# Central_Control.net
KiCad netlist of a schematic drawn in EAGLE
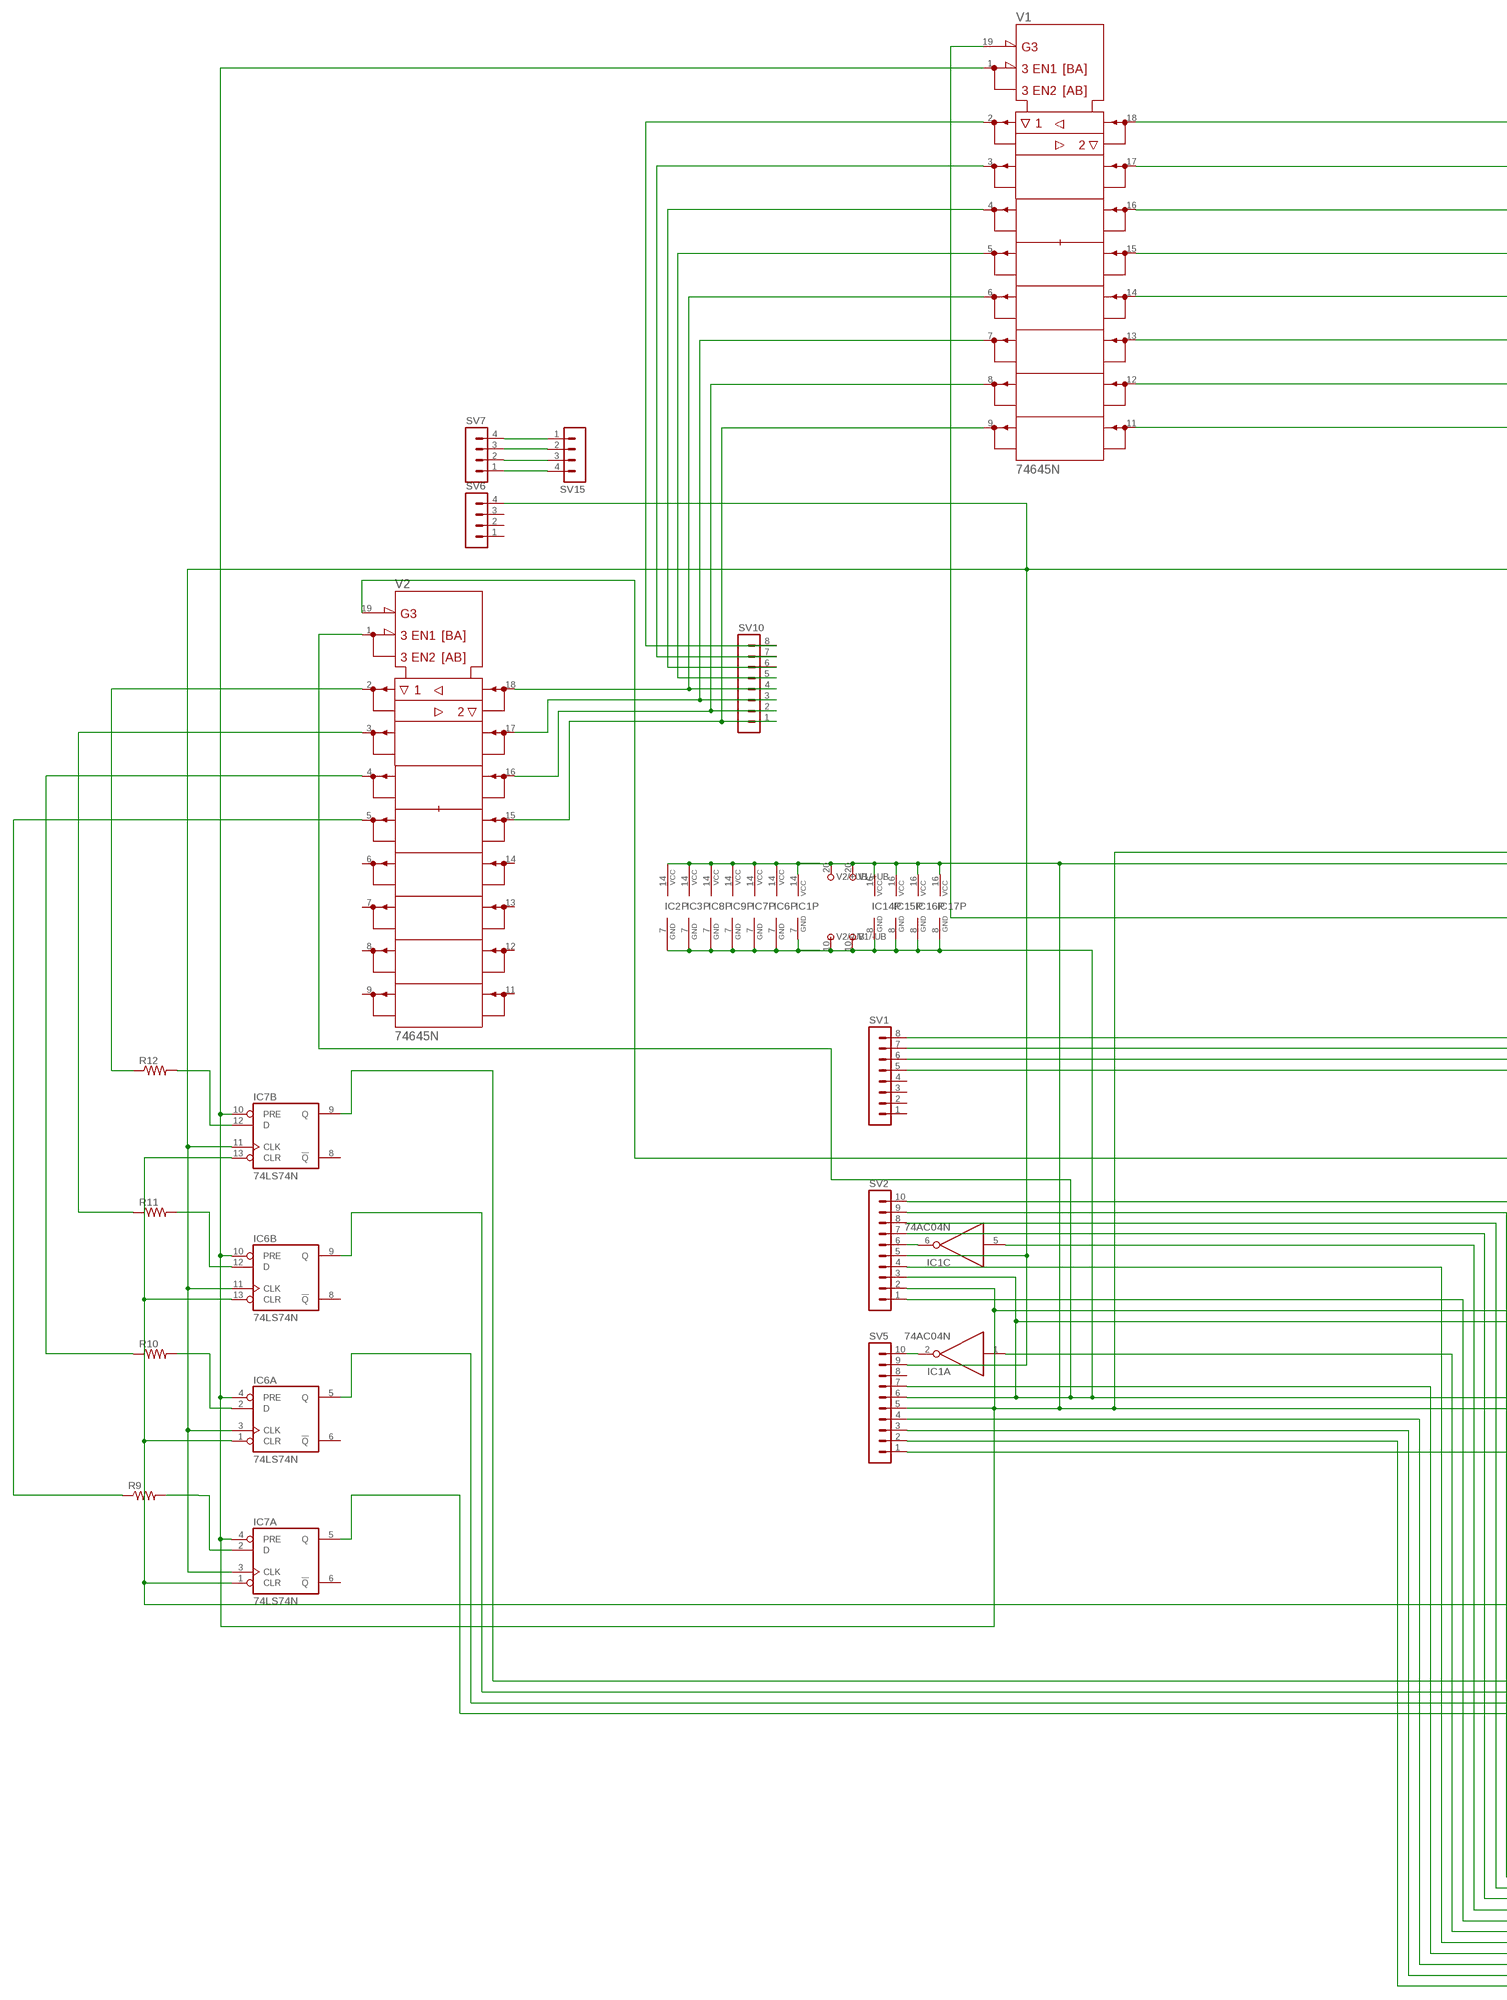
[diagram p0: schematic, sheet 1, part 1 of 3]
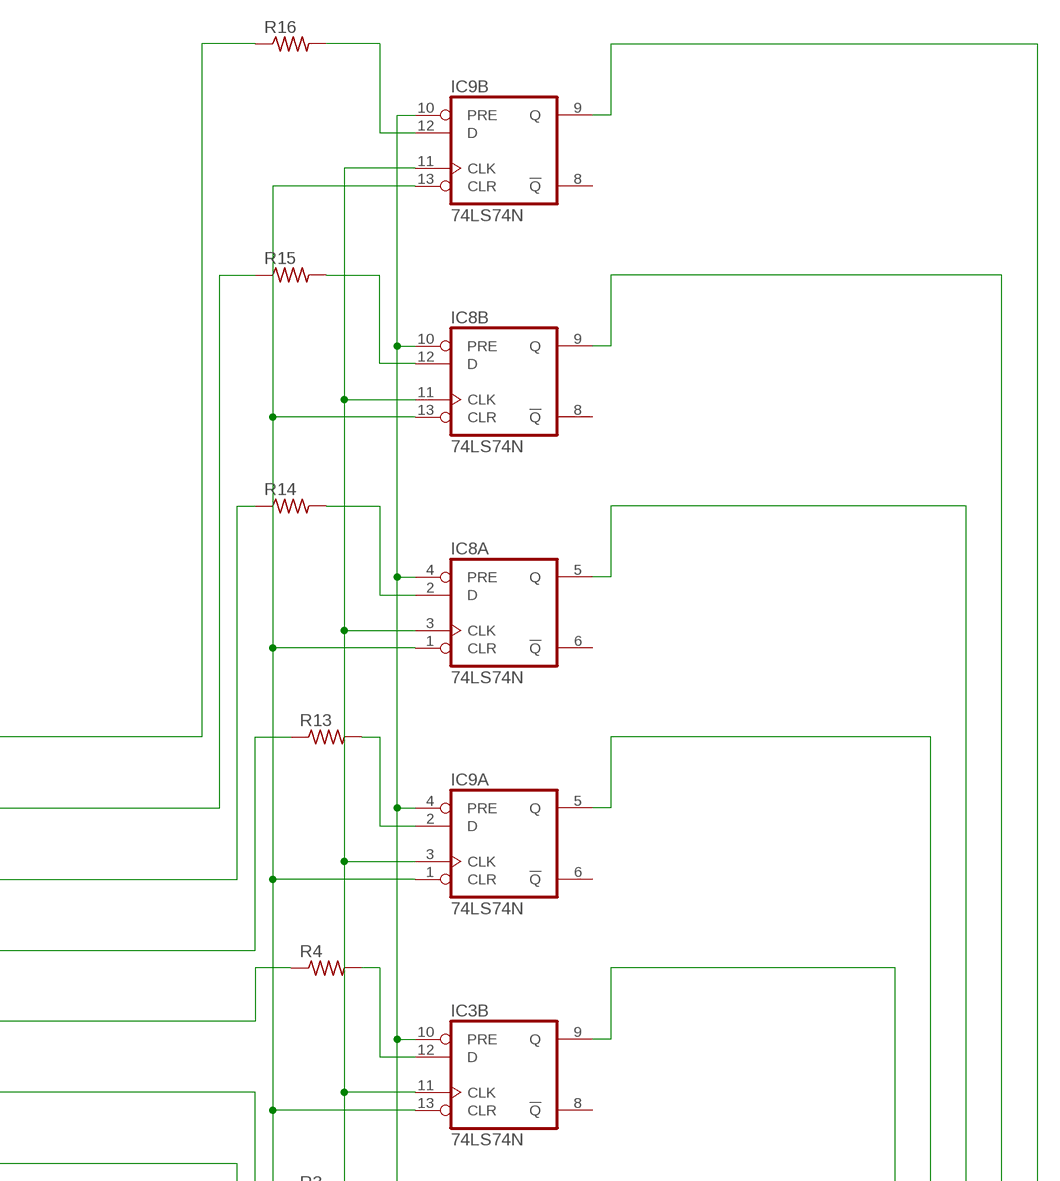
[diagram p1: schematic, sheet 1, part 2 of 3]
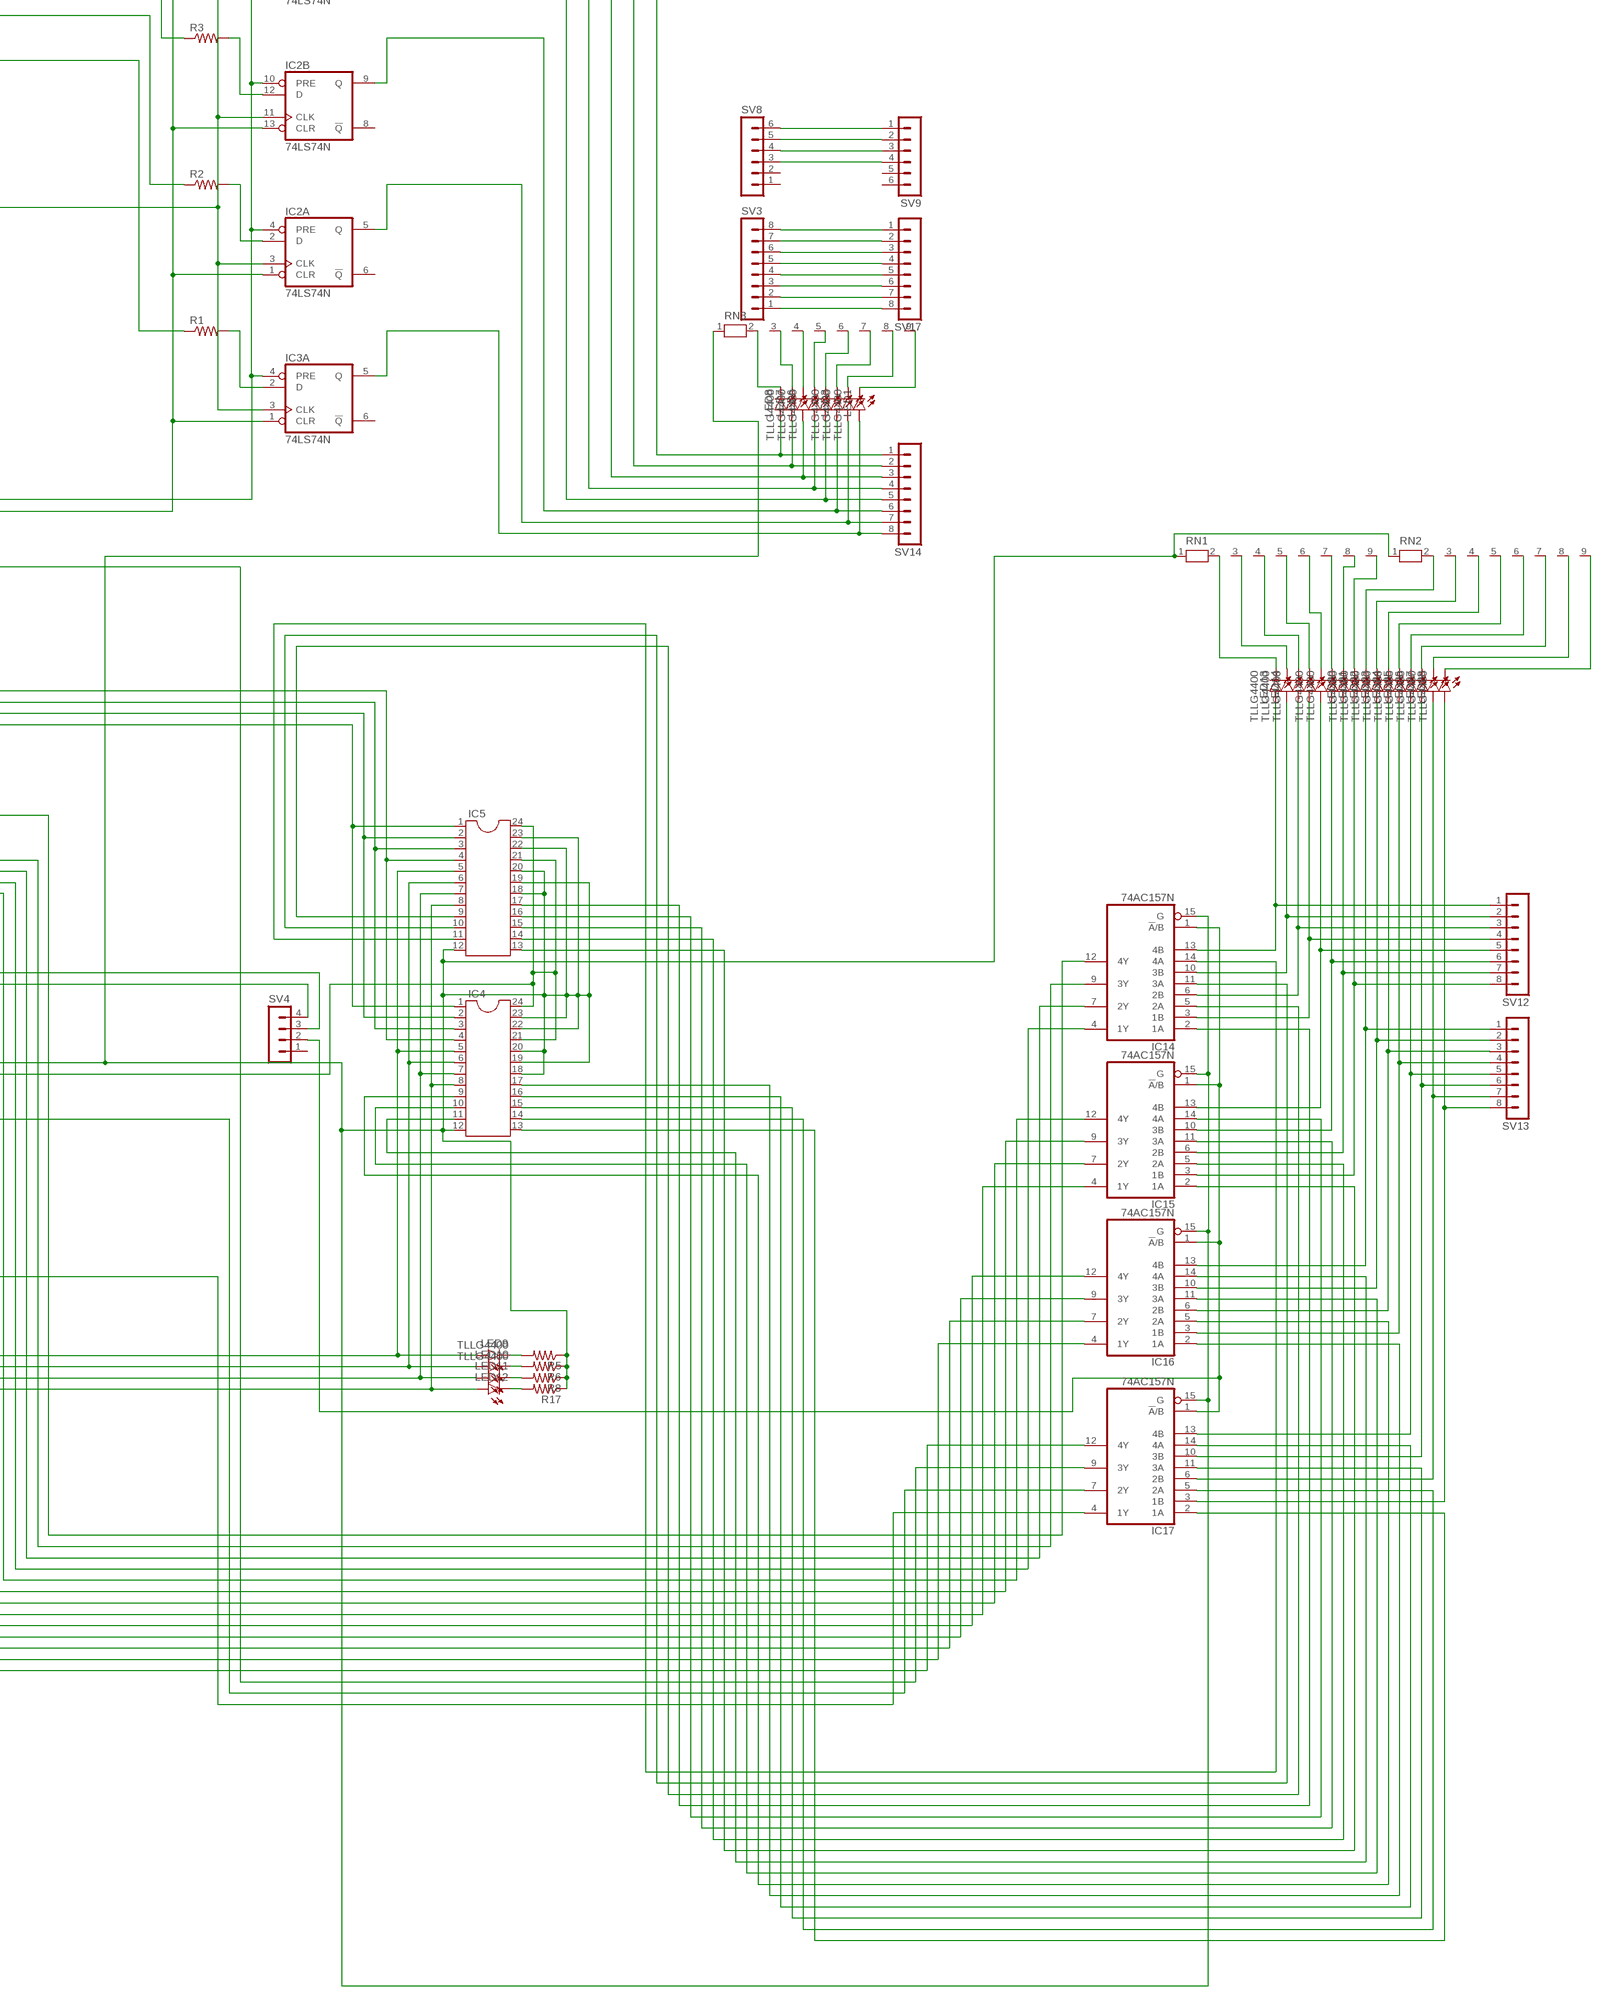
[diagram p2: schematic, sheet 1, part 3 of 3]

(export (version "E")
  (design (tool "Eeschema 10.0.6"))
  (components
    (comp (ref "IC1")
      (value "74AC04N")
      (footprint "eagle-import:DIL14")
      (libsource (lib "eagle-import") (part "7404NAC"))
    )
    (comp (ref "IC2")
      (value "74LS74N")
      (footprint "eagle-import:DIL14")
      (libsource (lib "eagle-import") (part "7474NLS"))
    )
    (comp (ref "IC3")
      (value "74LS74N")
      (footprint "eagle-import:DIL14")
      (libsource (lib "eagle-import") (part "7474NLS"))
    )
    (comp (ref "IC4")
      (value "DIL24-6")
      (footprint "eagle-import:DIL24-6")
      (libsource (lib "eagle-import") (part "DIL24-6"))
    )
    (comp (ref "IC5")
      (value "DIL24-6")
      (footprint "eagle-import:DIL24-6")
      (libsource (lib "eagle-import") (part "DIL24-6"))
    )
    (comp (ref "IC6")
      (value "74LS74N")
      (footprint "eagle-import:DIL14")
      (libsource (lib "eagle-import") (part "7474NLS"))
    )
    (comp (ref "IC7")
      (value "74LS74N")
      (footprint "eagle-import:DIL14")
      (libsource (lib "eagle-import") (part "7474NLS"))
    )
    (comp (ref "IC8")
      (value "74LS74N")
      (footprint "eagle-import:DIL14")
      (libsource (lib "eagle-import") (part "7474NLS"))
    )
    (comp (ref "IC9")
      (value "74LS74N")
      (footprint "eagle-import:DIL14")
      (libsource (lib "eagle-import") (part "7474NLS"))
    )
    (comp (ref "IC14")
      (value "74AC157N")
      (footprint "eagle-import:DIL16")
      (libsource (lib "eagle-import") (part "74157NAC"))
    )
    (comp (ref "IC15")
      (value "74AC157N")
      (footprint "eagle-import:DIL16")
      (libsource (lib "eagle-import") (part "74157NAC"))
    )
    (comp (ref "IC16")
      (value "74AC157N")
      (footprint "eagle-import:DIL16")
      (libsource (lib "eagle-import") (part "74157NAC"))
    )
    (comp (ref "IC17")
      (value "74AC157N")
      (footprint "eagle-import:DIL16")
      (libsource (lib "eagle-import") (part "74157NAC"))
    )
    (comp (ref "LED1")
      (value "TLLG4400")
      (footprint "eagle-import:LED3MM")
      (fields (field (name "MF") "VISHAY SEMICONDUCTOR"))
      (libsource (lib "eagle-import") (part "TLLG4400"))
    )
    (comp (ref "LED2")
      (value "TLLG4400")
      (footprint "eagle-import:LED3MM")
      (fields (field (name "MF") "VISHAY SEMICONDUCTOR"))
      (libsource (lib "eagle-import") (part "TLLG4400"))
    )
    (comp (ref "LED3")
      (value "TLLG4400")
      (footprint "eagle-import:LED3MM")
      (fields (field (name "MF") "VISHAY SEMICONDUCTOR"))
      (libsource (lib "eagle-import") (part "TLLG4400"))
    )
    (comp (ref "LED4")
      (value "TLLG4400")
      (footprint "eagle-import:LED3MM")
      (fields (field (name "MF") "VISHAY SEMICONDUCTOR"))
      (libsource (lib "eagle-import") (part "TLLG4400"))
    )
    (comp (ref "LED5")
      (value "TLLG4400")
      (footprint "eagle-import:LED3MM")
      (fields (field (name "MF") "VISHAY SEMICONDUCTOR"))
      (libsource (lib "eagle-import") (part "TLLG4400"))
    )
    (comp (ref "LED6")
      (value "TLLG4400")
      (footprint "eagle-import:LED3MM")
      (fields (field (name "MF") "VISHAY SEMICONDUCTOR"))
      (libsource (lib "eagle-import") (part "TLLG4400"))
    )
    (comp (ref "LED7")
      (value "TLLG4400")
      (footprint "eagle-import:LED3MM")
      (fields (field (name "MF") "VISHAY SEMICONDUCTOR"))
      (libsource (lib "eagle-import") (part "TLLG4400"))
    )
    (comp (ref "LED8")
      (value "TLLG4400")
      (footprint "eagle-import:LED3MM")
      (fields (field (name "MF") "VISHAY SEMICONDUCTOR"))
      (libsource (lib "eagle-import") (part "TLLG4400"))
    )
    (comp (ref "LED9")
      (value "TLLG4400")
      (footprint "eagle-import:LED3MM")
      (fields (field (name "MF") "VISHAY SEMICONDUCTOR"))
      (libsource (lib "eagle-import") (part "TLLG4400"))
    )
    (comp (ref "LED10")
      (value "TLLG4400")
      (footprint "eagle-import:LED3MM")
      (fields (field (name "MF") "VISHAY SEMICONDUCTOR"))
      (libsource (lib "eagle-import") (part "TLLG4400"))
    )
    (comp (ref "LED11")
      (value "TLLG4400")
      (footprint "eagle-import:LED3MM")
      (fields (field (name "MF") "VISHAY SEMICONDUCTOR"))
      (libsource (lib "eagle-import") (part "TLLG4400"))
    )
    (comp (ref "LED12")
      (value "TLLG4400")
      (footprint "eagle-import:LED3MM")
      (fields (field (name "MF") "VISHAY SEMICONDUCTOR"))
      (libsource (lib "eagle-import") (part "TLLG4400"))
    )
    (comp (ref "LED13")
      (value "TLLG4400")
      (footprint "eagle-import:LED3MM")
      (fields (field (name "MF") "VISHAY SEMICONDUCTOR"))
      (libsource (lib "eagle-import") (part "TLLG4400"))
    )
    (comp (ref "LED14")
      (value "TLLG4400")
      (footprint "eagle-import:LED3MM")
      (fields (field (name "MF") "VISHAY SEMICONDUCTOR"))
      (libsource (lib "eagle-import") (part "TLLG4400"))
    )
    (comp (ref "LED15")
      (value "TLLG4400")
      (footprint "eagle-import:LED3MM")
      (fields (field (name "MF") "VISHAY SEMICONDUCTOR"))
      (libsource (lib "eagle-import") (part "TLLG4400"))
    )
    (comp (ref "LED16")
      (value "TLLG4400")
      (footprint "eagle-import:LED3MM")
      (fields (field (name "MF") "VISHAY SEMICONDUCTOR"))
      (libsource (lib "eagle-import") (part "TLLG4400"))
    )
    (comp (ref "LED18")
      (value "TLLG4400")
      (footprint "eagle-import:LED3MM")
      (fields (field (name "MF") "VISHAY SEMICONDUCTOR"))
      (libsource (lib "eagle-import") (part "TLLG4400"))
    )
    (comp (ref "LED19")
      (value "TLLG4400")
      (footprint "eagle-import:LED3MM")
      (fields (field (name "MF") "VISHAY SEMICONDUCTOR"))
      (libsource (lib "eagle-import") (part "TLLG4400"))
    )
    (comp (ref "LED20")
      (value "TLLG4400")
      (footprint "eagle-import:LED3MM")
      (fields (field (name "MF") "VISHAY SEMICONDUCTOR"))
      (libsource (lib "eagle-import") (part "TLLG4400"))
    )
    (comp (ref "LED21")
      (value "TLLG4400")
      (footprint "eagle-import:LED3MM")
      (fields (field (name "MF") "VISHAY SEMICONDUCTOR"))
      (libsource (lib "eagle-import") (part "TLLG4400"))
    )
    (comp (ref "LED22")
      (value "TLLG4400")
      (footprint "eagle-import:LED3MM")
      (fields (field (name "MF") "VISHAY SEMICONDUCTOR"))
      (libsource (lib "eagle-import") (part "TLLG4400"))
    )
    (comp (ref "LED23")
      (value "TLLG4400")
      (footprint "eagle-import:LED3MM")
      (fields (field (name "MF") "VISHAY SEMICONDUCTOR"))
      (libsource (lib "eagle-import") (part "TLLG4400"))
    )
    (comp (ref "LED24")
      (value "TLLG4400")
      (footprint "eagle-import:LED3MM")
      (fields (field (name "MF") "VISHAY SEMICONDUCTOR"))
      (libsource (lib "eagle-import") (part "TLLG4400"))
    )
    (comp (ref "LED25")
      (value "TLLG4400")
      (footprint "eagle-import:LED3MM")
      (fields (field (name "MF") "VISHAY SEMICONDUCTOR"))
      (libsource (lib "eagle-import") (part "TLLG4400"))
    )
    (comp (ref "LED26")
      (value "TLLG4400")
      (footprint "eagle-import:LED3MM")
      (fields (field (name "MF") "VISHAY SEMICONDUCTOR"))
      (libsource (lib "eagle-import") (part "TLLG4400"))
    )
    (comp (ref "LED27")
      (value "TLLG4400")
      (footprint "eagle-import:LED3MM")
      (fields (field (name "MF") "VISHAY SEMICONDUCTOR"))
      (libsource (lib "eagle-import") (part "TLLG4400"))
    )
    (comp (ref "LED28")
      (value "TLLG4400")
      (footprint "eagle-import:LED3MM")
      (fields (field (name "MF") "VISHAY SEMICONDUCTOR"))
      (libsource (lib "eagle-import") (part "TLLG4400"))
    )
    (comp (ref "LED29")
      (value "TLLG4400")
      (footprint "eagle-import:LED3MM")
      (fields (field (name "MF") "VISHAY SEMICONDUCTOR"))
      (libsource (lib "eagle-import") (part "TLLG4400"))
    )
    (comp (ref "R1")
      (value "R-US_0207/2V")
      (footprint "eagle-import:0207_2V")
      (libsource (lib "eagle-import") (part "R-US_0207/2V"))
    )
    (comp (ref "R2")
      (value "R-US_0207/2V")
      (footprint "eagle-import:0207_2V")
      (libsource (lib "eagle-import") (part "R-US_0207/2V"))
    )
    (comp (ref "R3")
      (value "R-US_0207/2V")
      (footprint "eagle-import:0207_2V")
      (libsource (lib "eagle-import") (part "R-US_0207/2V"))
    )
    (comp (ref "R4")
      (value "R-US_0207/2V")
      (footprint "eagle-import:0207_2V")
      (libsource (lib "eagle-import") (part "R-US_0207/2V"))
    )
    (comp (ref "R5")
      (value "R-US_0207/2V")
      (footprint "eagle-import:0207_2V")
      (libsource (lib "eagle-import") (part "R-US_0207/2V"))
    )
    (comp (ref "R6")
      (value "R-US_0207/2V")
      (footprint "eagle-import:0207_2V")
      (libsource (lib "eagle-import") (part "R-US_0207/2V"))
    )
    (comp (ref "R8")
      (value "R-US_0207/2V")
      (footprint "eagle-import:0207_2V")
      (libsource (lib "eagle-import") (part "R-US_0207/2V"))
    )
    (comp (ref "R9")
      (value "R-US_0207/2V")
      (footprint "eagle-import:0207_2V")
      (libsource (lib "eagle-import") (part "R-US_0207/2V"))
    )
    (comp (ref "R10")
      (value "R-US_0207/2V")
      (footprint "eagle-import:0207_2V")
      (libsource (lib "eagle-import") (part "R-US_0207/2V"))
    )
    (comp (ref "R11")
      (value "R-US_0207/2V")
      (footprint "eagle-import:0207_2V")
      (libsource (lib "eagle-import") (part "R-US_0207/2V"))
    )
    (comp (ref "R12")
      (value "R-US_0207/2V")
      (footprint "eagle-import:0207_2V")
      (libsource (lib "eagle-import") (part "R-US_0207/2V"))
    )
    (comp (ref "R13")
      (value "R-US_0207/2V")
      (footprint "eagle-import:0207_2V")
      (libsource (lib "eagle-import") (part "R-US_0207/2V"))
    )
    (comp (ref "R14")
      (value "R-US_0207/2V")
      (footprint "eagle-import:0207_2V")
      (libsource (lib "eagle-import") (part "R-US_0207/2V"))
    )
    (comp (ref "R15")
      (value "R-US_0207/2V")
      (footprint "eagle-import:0207_2V")
      (libsource (lib "eagle-import") (part "R-US_0207/2V"))
    )
    (comp (ref "R16")
      (value "R-US_0207/2V")
      (footprint "eagle-import:0207_2V")
      (libsource (lib "eagle-import") (part "R-US_0207/2V"))
    )
    (comp (ref "R17")
      (value "R-US_0207/2V")
      (footprint "eagle-import:0207_2V")
      (libsource (lib "eagle-import") (part "R-US_0207/2V"))
    )
    (comp (ref "RN1")
      (value "RN08")
      (footprint "eagle-import:RN-9")
      (libsource (lib "eagle-import") (part "RN08"))
    )
    (comp (ref "RN2")
      (value "RN08")
      (footprint "eagle-import:RN-9")
      (libsource (lib "eagle-import") (part "RN08"))
    )
    (comp (ref "RN3")
      (value "RN08")
      (footprint "eagle-import:RN-9")
      (libsource (lib "eagle-import") (part "RN08"))
    )
    (comp (ref "SV1")
      (value "MA08-1")
      (footprint "eagle-import:MA08-1")
      (libsource (lib "eagle-import") (part "MA08-1"))
    )
    (comp (ref "SV2")
      (value "MA10-1")
      (footprint "eagle-import:MA10-1")
      (libsource (lib "eagle-import") (part "MA10-1"))
    )
    (comp (ref "SV3")
      (value "MA08-1")
      (footprint "eagle-import:MA08-1")
      (libsource (lib "eagle-import") (part "MA08-1"))
    )
    (comp (ref "SV4")
      (value "MA04-1")
      (footprint "eagle-import:MA04-1")
      (libsource (lib "eagle-import") (part "MA04-1"))
    )
    (comp (ref "SV5")
      (value "MA10-1")
      (footprint "eagle-import:MA10-1")
      (libsource (lib "eagle-import") (part "MA10-1"))
    )
    (comp (ref "SV6")
      (value "MA04-1")
      (footprint "eagle-import:MA04-1")
      (libsource (lib "eagle-import") (part "MA04-1"))
    )
    (comp (ref "SV7")
      (value "MA04-1")
      (footprint "eagle-import:MA04-1")
      (libsource (lib "eagle-import") (part "MA04-1"))
    )
    (comp (ref "SV8")
      (value "MA06-1")
      (footprint "eagle-import:MA06-1")
      (libsource (lib "eagle-import") (part "MA06-1"))
    )
    (comp (ref "SV9")
      (value "MA06-1")
      (footprint "eagle-import:MA06-1")
      (libsource (lib "eagle-import") (part "MA06-1"))
    )
    (comp (ref "SV10")
      (value "MA08-1")
      (footprint "eagle-import:MA08-1")
      (libsource (lib "eagle-import") (part "MA08-1"))
    )
    (comp (ref "SV12")
      (value "MA08-1")
      (footprint "eagle-import:MA08-1")
      (libsource (lib "eagle-import") (part "MA08-1"))
    )
    (comp (ref "SV13")
      (value "MA08-1")
      (footprint "eagle-import:MA08-1")
      (libsource (lib "eagle-import") (part "MA08-1"))
    )
    (comp (ref "SV14")
      (value "MA08-1")
      (footprint "eagle-import:MA08-1")
      (libsource (lib "eagle-import") (part "MA08-1"))
    )
    (comp (ref "SV15")
      (value "MA04-1")
      (footprint "eagle-import:MA04-1")
      (libsource (lib "eagle-import") (part "MA04-1"))
    )
    (comp (ref "SV17")
      (value "MA08-1")
      (footprint "eagle-import:MA08-1")
      (libsource (lib "eagle-import") (part "MA08-1"))
    )
    (comp (ref "V1")
      (value "74645N")
      (footprint "eagle-import:DIL20")
      (libsource (lib "eagle-import") (part "74645N"))
    )
    (comp (ref "V2")
      (value "74645N")
      (footprint "eagle-import:DIL20")
      (libsource (lib "eagle-import") (part "74645N"))
    )
  )
  (nets
    (net (code "1") (name "Net-(IC1A-O)") (class "Default")
      (node (ref "IC1") (pin "2") (pinfunction "O_2") (pintype "output"))
      (node (ref "SV5") (pin "10") (pinfunction "10_10") (pintype "passive"))
    )
    (net (code "2") (name "Net-(IC1C-O)") (class "Default")
      (node (ref "IC1") (pin "6") (pinfunction "O_6") (pintype "output"))
      (node (ref "SV2") (pin "6") (pinfunction "6_6") (pintype "passive"))
    )
    (net (code "3") (name "Net-(IC2A-CLK)") (class "Default")
      (node (ref "IC2") (pin "11") (pinfunction "CLK_11") (pintype "input"))
      (node (ref "IC2") (pin "3") (pinfunction "CLK_3") (pintype "input"))
      (node (ref "IC3") (pin "11") (pinfunction "CLK_11") (pintype "input"))
      (node (ref "IC3") (pin "3") (pinfunction "CLK_3") (pintype "input"))
      (node (ref "IC6") (pin "11") (pinfunction "CLK_11") (pintype "input"))
      (node (ref "IC6") (pin "3") (pinfunction "CLK_3") (pintype "input"))
      (node (ref "IC7") (pin "11") (pinfunction "CLK_11") (pintype "input"))
      (node (ref "IC7") (pin "3") (pinfunction "CLK_3") (pintype "input"))
      (node (ref "IC8") (pin "11") (pinfunction "CLK_11") (pintype "input"))
      (node (ref "IC8") (pin "3") (pinfunction "CLK_3") (pintype "input"))
      (node (ref "IC9") (pin "11") (pinfunction "CLK_11") (pintype "input"))
      (node (ref "IC9") (pin "3") (pinfunction "CLK_3") (pintype "input"))
      (node (ref "SV2") (pin "5") (pinfunction "5_5") (pintype "passive"))
      (node (ref "SV5") (pin "9") (pinfunction "9_9") (pintype "passive"))
      (node (ref "SV6") (pin "4") (pinfunction "4_4") (pintype "passive"))
    )
    (net (code "4") (name "Net-(IC2A-D)") (class "Default")
      (node (ref "IC2") (pin "2") (pinfunction "D_2") (pintype "input"))
      (node (ref "R2") (pin "2") (pinfunction "2_2") (pintype "passive"))
    )
    (net (code "5") (name "Net-(IC2A-Q)") (class "Default")
      (node (ref "IC2") (pin "5") (pinfunction "Q_5") (pintype "output"))
      (node (ref "LED2") (pin "A") (pinfunction "A_A") (pintype "passive"))
      (node (ref "SV14") (pin "7") (pinfunction "7_7") (pintype "passive"))
    )
    (net (code "6") (name "Net-(IC2B-D)") (class "Default")
      (node (ref "IC2") (pin "12") (pinfunction "D_12") (pintype "input"))
      (node (ref "R3") (pin "2") (pinfunction "2_2") (pintype "passive"))
    )
    (net (code "7") (name "Net-(IC2B-Q)") (class "Default")
      (node (ref "IC2") (pin "9") (pinfunction "Q_9") (pintype "output"))
      (node (ref "LED3") (pin "A") (pinfunction "A_A") (pintype "passive"))
      (node (ref "SV14") (pin "6") (pinfunction "6_6") (pintype "passive"))
    )
    (net (code "8") (name "Net-(IC3A-D)") (class "Default")
      (node (ref "IC3") (pin "2") (pinfunction "D_2") (pintype "input"))
      (node (ref "R1") (pin "2") (pinfunction "2_2") (pintype "passive"))
    )
    (net (code "9") (name "Net-(IC3A-Q)") (class "Default")
      (node (ref "IC3") (pin "5") (pinfunction "Q_5") (pintype "output"))
      (node (ref "LED1") (pin "A") (pinfunction "A_A") (pintype "passive"))
      (node (ref "SV14") (pin "8") (pinfunction "8_8") (pintype "passive"))
    )
    (net (code "10") (name "Net-(IC3B-D)") (class "Default")
      (node (ref "IC3") (pin "12") (pinfunction "D_12") (pintype "input"))
      (node (ref "R4") (pin "2") (pinfunction "2_2") (pintype "passive"))
    )
    (net (code "11") (name "Net-(IC3B-Q)") (class "Default")
      (node (ref "IC3") (pin "9") (pinfunction "Q_9") (pintype "output"))
      (node (ref "LED4") (pin "A") (pinfunction "A_A") (pintype "passive"))
      (node (ref "SV14") (pin "5") (pinfunction "5_5") (pintype "passive"))
    )
    (net (code "12") (name "Net-(IC4-Pad1)") (class "Default")
      (node (ref "IC4") (pin "1") (pinfunction "1_1") (pintype "passive"))
      (node (ref "IC5") (pin "1") (pinfunction "1_1") (pintype "passive"))
      (node (ref "SV1") (pin "5") (pinfunction "5_5") (pintype "passive"))
    )
    (net (code "13") (name "Net-(IC4-Pad2)") (class "Default")
      (node (ref "IC4") (pin "2") (pinfunction "2_2") (pintype "passive"))
      (node (ref "IC5") (pin "2") (pinfunction "2_2") (pintype "passive"))
      (node (ref "SV1") (pin "6") (pinfunction "6_6") (pintype "passive"))
    )
    (net (code "14") (name "Net-(IC4-Pad3)") (class "Default")
      (node (ref "IC4") (pin "3") (pinfunction "3_3") (pintype "passive"))
      (node (ref "IC5") (pin "3") (pinfunction "3_3") (pintype "passive"))
      (node (ref "SV1") (pin "7") (pinfunction "7_7") (pintype "passive"))
    )
    (net (code "15") (name "Net-(IC4-Pad4)") (class "Default")
      (node (ref "IC4") (pin "4") (pinfunction "4_4") (pintype "passive"))
      (node (ref "IC5") (pin "4") (pinfunction "4_4") (pintype "passive"))
      (node (ref "SV1") (pin "8") (pinfunction "8_8") (pintype "passive"))
    )
    (net (code "16") (name "Net-(IC6A-D)") (class "Default")
      (node (ref "IC6") (pin "2") (pinfunction "D_2") (pintype "input"))
      (node (ref "R10") (pin "2") (pinfunction "2_2") (pintype "passive"))
    )
    (net (code "17") (name "Net-(IC6A-Q)") (class "Default")
      (node (ref "IC4") (pin "7") (pinfunction "7_7") (pintype "passive"))
      (node (ref "IC5") (pin "7") (pinfunction "7_7") (pintype "passive"))
      (node (ref "IC6") (pin "5") (pinfunction "Q_5") (pintype "output"))
      (node (ref "LED11") (pin "A") (pinfunction "A_A") (pintype "passive"))
    )
    (net (code "18") (name "Net-(IC6B-D)") (class "Default")
      (node (ref "IC6") (pin "12") (pinfunction "D_12") (pintype "input"))
      (node (ref "R11") (pin "2") (pinfunction "2_2") (pintype "passive"))
    )
    (net (code "19") (name "Net-(IC6B-Q)") (class "Default")
      (node (ref "IC4") (pin "6") (pinfunction "6_6") (pintype "passive"))
      (node (ref "IC5") (pin "6") (pinfunction "6_6") (pintype "passive"))
      (node (ref "IC6") (pin "9") (pinfunction "Q_9") (pintype "output"))
      (node (ref "LED10") (pin "A") (pinfunction "A_A") (pintype "passive"))
    )
    (net (code "20") (name "Net-(IC7A-D)") (class "Default")
      (node (ref "IC7") (pin "2") (pinfunction "D_2") (pintype "input"))
      (node (ref "R9") (pin "2") (pinfunction "2_2") (pintype "passive"))
    )
    (net (code "21") (name "Net-(IC7A-Q)") (class "Default")
      (node (ref "IC4") (pin "8") (pinfunction "8_8") (pintype "passive"))
      (node (ref "IC5") (pin "8") (pinfunction "8_8") (pintype "passive"))
      (node (ref "IC7") (pin "5") (pinfunction "Q_5") (pintype "output"))
      (node (ref "LED12") (pin "A") (pinfunction "A_A") (pintype "passive"))
    )
    (net (code "22") (name "Net-(IC7B-D)") (class "Default")
      (node (ref "IC7") (pin "12") (pinfunction "D_12") (pintype "input"))
      (node (ref "R12") (pin "2") (pinfunction "2_2") (pintype "passive"))
    )
    (net (code "23") (name "Net-(IC7B-Q)") (class "Default")
      (node (ref "IC4") (pin "5") (pinfunction "5_5") (pintype "passive"))
      (node (ref "IC5") (pin "5") (pinfunction "5_5") (pintype "passive"))
      (node (ref "IC7") (pin "9") (pinfunction "Q_9") (pintype "output"))
      (node (ref "LED9") (pin "A") (pinfunction "A_A") (pintype "passive"))
    )
    (net (code "24") (name "Net-(IC8A-D)") (class "Default")
      (node (ref "IC8") (pin "2") (pinfunction "D_2") (pintype "input"))
      (node (ref "R14") (pin "2") (pinfunction "2_2") (pintype "passive"))
    )
    (net (code "25") (name "Net-(IC8A-Q)") (class "Default")
      (node (ref "IC8") (pin "5") (pinfunction "Q_5") (pintype "output"))
      (node (ref "LED6") (pin "A") (pinfunction "A_A") (pintype "passive"))
      (node (ref "SV14") (pin "3") (pinfunction "3_3") (pintype "passive"))
    )
    (net (code "26") (name "Net-(IC8B-D)") (class "Default")
      (node (ref "IC8") (pin "12") (pinfunction "D_12") (pintype "input"))
      (node (ref "R15") (pin "2") (pinfunction "2_2") (pintype "passive"))
    )
    (net (code "27") (name "Net-(IC8B-Q)") (class "Default")
      (node (ref "IC8") (pin "9") (pinfunction "Q_9") (pintype "output"))
      (node (ref "LED7") (pin "A") (pinfunction "A_A") (pintype "passive"))
      (node (ref "SV14") (pin "2") (pinfunction "2_2") (pintype "passive"))
    )
    (net (code "28") (name "Net-(IC9A-D)") (class "Default")
      (node (ref "IC9") (pin "2") (pinfunction "D_2") (pintype "input"))
      (node (ref "R13") (pin "2") (pinfunction "2_2") (pintype "passive"))
    )
    (net (code "29") (name "Net-(IC9A-Q)") (class "Default")
      (node (ref "IC9") (pin "5") (pinfunction "Q_5") (pintype "output"))
      (node (ref "LED5") (pin "A") (pinfunction "A_A") (pintype "passive"))
      (node (ref "SV14") (pin "4") (pinfunction "4_4") (pintype "passive"))
    )
    (net (code "30") (name "Net-(IC9B-D)") (class "Default")
      (node (ref "IC9") (pin "12") (pinfunction "D_12") (pintype "input"))
      (node (ref "R16") (pin "2") (pinfunction "2_2") (pintype "passive"))
    )
    (net (code "31") (name "Net-(IC9B-Q)") (class "Default")
      (node (ref "IC9") (pin "9") (pinfunction "Q_9") (pintype "output"))
      (node (ref "LED8") (pin "A") (pinfunction "A_A") (pintype "passive"))
      (node (ref "SV14") (pin "1") (pinfunction "1_1") (pintype "passive"))
    )
    (net (code "32") (name "Net-(IC14A-1A)") (class "Default")
      (node (ref "IC14") (pin "2") (pinfunction "1A_2") (pintype "input"))
      (node (ref "IC5") (pin "17") (pinfunction "17_17") (pintype "passive"))
    )
    (net (code "33") (name "Net-(IC14A-1B)") (class "Default")
      (node (ref "IC14") (pin "3") (pinfunction "1B_3") (pintype "input"))
      (node (ref "LED16") (pin "A") (pinfunction "A_A") (pintype "passive"))
      (node (ref "SV12") (pin "4") (pinfunction "4_4") (pintype "passive"))
    )
    (net (code "34") (name "Net-(IC14A-1Y)") (class "Default")
      (node (ref "IC14") (pin "4") (pinfunction "1Y_4") (pintype "output"))
      (node (ref "SV2") (pin "8") (pinfunction "8_8") (pintype "passive"))
    )
    (net (code "35") (name "Net-(IC14A-2A)") (class "Default")
      (node (ref "IC14") (pin "5") (pinfunction "2A_5") (pintype "input"))
      (node (ref "IC5") (pin "9") (pinfunction "9_9") (pintype "passive"))
    )
    (net (code "36") (name "Net-(IC14A-2B)") (class "Default")
      (node (ref "IC14") (pin "6") (pinfunction "2B_6") (pintype "input"))
      (node (ref "LED15") (pin "A") (pinfunction "A_A") (pintype "passive"))
      (node (ref "SV12") (pin "3") (pinfunction "3_3") (pintype "passive"))
    )
    (net (code "37") (name "Net-(IC14A-2Y)") (class "Default")
      (node (ref "IC14") (pin "7") (pinfunction "2Y_7") (pintype "output"))
      (node (ref "SV2") (pin "9") (pinfunction "9_9") (pintype "passive"))
    )
    (net (code "38") (name "Net-(IC14A-3A)") (class "Default")
      (node (ref "IC14") (pin "11") (pinfunction "3A_11") (pintype "input"))
      (node (ref "IC5") (pin "10") (pinfunction "10_10") (pintype "passive"))
    )
    (net (code "39") (name "Net-(IC14A-3B)") (class "Default")
      (node (ref "IC14") (pin "10") (pinfunction "3B_10") (pintype "input"))
      (node (ref "LED14") (pin "A") (pinfunction "A_A") (pintype "passive"))
      (node (ref "SV12") (pin "2") (pinfunction "2_2") (pintype "passive"))
    )
    (net (code "40") (name "Net-(IC14A-3Y)") (class "Default")
      (node (ref "IC14") (pin "9") (pinfunction "3Y_9") (pintype "output"))
      (node (ref "SV2") (pin "10") (pinfunction "10_10") (pintype "passive"))
    )
    (net (code "41") (name "Net-(IC14A-4A)") (class "Default")
      (node (ref "IC14") (pin "14") (pinfunction "4A_14") (pintype "input"))
      (node (ref "IC5") (pin "11") (pinfunction "11_11") (pintype "passive"))
    )
    (net (code "42") (name "Net-(IC14A-4B)") (class "Default")
      (node (ref "IC14") (pin "13") (pinfunction "4B_13") (pintype "input"))
      (node (ref "LED13") (pin "A") (pinfunction "A_A") (pintype "passive"))
      (node (ref "SV12") (pin "1") (pinfunction "1_1") (pintype "passive"))
    )
    (net (code "43") (name "Net-(IC14A-4Y)") (class "Default")
      (node (ref "IC14") (pin "12") (pinfunction "4Y_12") (pintype "output"))
      (node (ref "V2") (pin "19") (pinfunction "~{G}_19") (pintype "input"))
    )
    (net (code "44") (name "Net-(IC14A-G)") (class "Default")
      (node (ref "IC1") (pin "7") (pinfunction "GND_7") (pintype "power_in"))
      (node (ref "IC14") (pin "15") (pinfunction "G_15") (pintype "input"))
      (node (ref "IC14") (pin "8") (pinfunction "GND_8") (pintype "power_in"))
      (node (ref "IC15") (pin "15") (pinfunction "G_15") (pintype "input"))
      (node (ref "IC15") (pin "8") (pinfunction "GND_8") (pintype "power_in"))
      (node (ref "IC16") (pin "15") (pinfunction "G_15") (pintype "input"))
      (node (ref "IC16") (pin "8") (pinfunction "GND_8") (pintype "power_in"))
      (node (ref "IC17") (pin "15") (pinfunction "G_15") (pintype "input"))
      (node (ref "IC17") (pin "8") (pinfunction "GND_8") (pintype "power_in"))
      (node (ref "IC2") (pin "7") (pinfunction "GND_7") (pintype "power_in"))
      (node (ref "IC3") (pin "7") (pinfunction "GND_7") (pintype "power_in"))
      (node (ref "IC4") (pin "12") (pinfunction "12_12") (pintype "passive"))
      (node (ref "IC4") (pin "18") (pinfunction "18_18") (pintype "passive"))
      (node (ref "IC4") (pin "19") (pinfunction "19_19") (pintype "passive"))
      (node (ref "IC4") (pin "20") (pinfunction "20_20") (pintype "passive"))
      (node (ref "IC4") (pin "22") (pinfunction "22_22") (pintype "passive"))
      (node (ref "IC4") (pin "23") (pinfunction "23_23") (pintype "passive"))
      (node (ref "IC5") (pin "12") (pinfunction "12_12") (pintype "passive"))
      (node (ref "IC5") (pin "18") (pinfunction "18_18") (pintype "passive"))
      (node (ref "IC5") (pin "19") (pinfunction "19_19") (pintype "passive"))
      (node (ref "IC5") (pin "20") (pinfunction "20_20") (pintype "passive"))
      (node (ref "IC5") (pin "22") (pinfunction "22_22") (pintype "passive"))
      (node (ref "IC5") (pin "23") (pinfunction "23_23") (pintype "passive"))
      (node (ref "IC6") (pin "7") (pinfunction "GND_7") (pintype "power_in"))
      (node (ref "IC7") (pin "7") (pinfunction "GND_7") (pintype "power_in"))
      (node (ref "IC8") (pin "7") (pinfunction "GND_7") (pintype "power_in"))
      (node (ref "IC9") (pin "7") (pinfunction "GND_7") (pintype "power_in"))
      (node (ref "R17") (pin "1") (pinfunction "1_1") (pintype "passive"))
      (node (ref "R5") (pin "1") (pinfunction "1_1") (pintype "passive"))
      (node (ref "R6") (pin "1") (pinfunction "1_1") (pintype "passive"))
      (node (ref "R8") (pin "1") (pinfunction "1_1") (pintype "passive"))
      (node (ref "RN1") (pin "1") (pinfunction "1_1") (pintype "passive"))
      (node (ref "RN2") (pin "1") (pinfunction "1_1") (pintype "passive"))
      (node (ref "RN3") (pin "1") (pinfunction "1_1") (pintype "passive"))
      (node (ref "SV2") (pin "3") (pinfunction "3_3") (pintype "passive"))
      (node (ref "SV4") (pin "4") (pinfunction "4_4") (pintype "passive"))
      (node (ref "SV5") (pin "6") (pinfunction "6_6") (pintype "passive"))
      (node (ref "V1") (pin "10") (pinfunction "-UB_10") (pintype "power_in"))
      (node (ref "V2") (pin "1") (pinfunction "DIR_1") (pintype "input"))
      (node (ref "V2") (pin "10") (pinfunction "-UB_10") (pintype "power_in"))
    )
    (net (code "45") (name "Net-(IC14A-~{A}{slash}B)") (class "Default")
      (node (ref "IC14") (pin "1") (pinfunction "~{A}/B_1") (pintype "input"))
      (node (ref "IC15") (pin "1") (pinfunction "~{A}/B_1") (pintype "input"))
      (node (ref "IC16") (pin "1") (pinfunction "~{A}/B_1") (pintype "input"))
      (node (ref "IC17") (pin "1") (pinfunction "~{A}/B_1") (pintype "input"))
      (node (ref "SV4") (pin "2") (pinfunction "2_2") (pintype "passive"))
    )
    (net (code "46") (name "Net-(IC14B-VCC)") (class "Default")
      (node (ref "IC1") (pin "14") (pinfunction "VCC_14") (pintype "power_in"))
      (node (ref "IC14") (pin "16") (pinfunction "VCC_16") (pintype "power_in"))
      (node (ref "IC15") (pin "16") (pinfunction "VCC_16") (pintype "power_in"))
      (node (ref "IC16") (pin "16") (pinfunction "VCC_16") (pintype "power_in"))
      (node (ref "IC17") (pin "16") (pinfunction "VCC_16") (pintype "power_in"))
      (node (ref "IC2") (pin "1") (pinfunction "CLR_1") (pintype "input"))
      (node (ref "IC2") (pin "10") (pinfunction "PRE_10") (pintype "input"))
      (node (ref "IC2") (pin "13") (pinfunction "CLR_13") (pintype "input"))
      (node (ref "IC2") (pin "14") (pinfunction "VCC_14") (pintype "power_in"))
      (node (ref "IC2") (pin "4") (pinfunction "PRE_4") (pintype "input"))
      (node (ref "IC3") (pin "1") (pinfunction "CLR_1") (pintype "input"))
      (node (ref "IC3") (pin "10") (pinfunction "PRE_10") (pintype "input"))
      (node (ref "IC3") (pin "13") (pinfunction "CLR_13") (pintype "input"))
      (node (ref "IC3") (pin "14") (pinfunction "VCC_14") (pintype "power_in"))
      (node (ref "IC3") (pin "4") (pinfunction "PRE_4") (pintype "input"))
      (node (ref "IC4") (pin "21") (pinfunction "21_21") (pintype "passive"))
      (node (ref "IC4") (pin "24") (pinfunction "24_24") (pintype "passive"))
      (node (ref "IC5") (pin "21") (pinfunction "21_21") (pintype "passive"))
      (node (ref "IC5") (pin "24") (pinfunction "24_24") (pintype "passive"))
      (node (ref "IC6") (pin "10") (pinfunction "PRE_10") (pintype "input"))
      (node (ref "IC6") (pin "14") (pinfunction "VCC_14") (pintype "power_in"))
      (node (ref "IC6") (pin "4") (pinfunction "PRE_4") (pintype "input"))
      (node (ref "IC7") (pin "10") (pinfunction "PRE_10") (pintype "input"))
      (node (ref "IC7") (pin "14") (pinfunction "VCC_14") (pintype "power_in"))
      (node (ref "IC7") (pin "4") (pinfunction "PRE_4") (pintype "input"))
      (node (ref "IC8") (pin "1") (pinfunction "CLR_1") (pintype "input"))
      (node (ref "IC8") (pin "10") (pinfunction "PRE_10") (pintype "input"))
      (node (ref "IC8") (pin "13") (pinfunction "CLR_13") (pintype "input"))
      (node (ref "IC8") (pin "14") (pinfunction "VCC_14") (pintype "power_in"))
      (node (ref "IC8") (pin "4") (pinfunction "PRE_4") (pintype "input"))
      (node (ref "IC9") (pin "1") (pinfunction "CLR_1") (pintype "input"))
      (node (ref "IC9") (pin "10") (pinfunction "PRE_10") (pintype "input"))
      (node (ref "IC9") (pin "13") (pinfunction "CLR_13") (pintype "input"))
      (node (ref "IC9") (pin "14") (pinfunction "VCC_14") (pintype "power_in"))
      (node (ref "IC9") (pin "4") (pinfunction "PRE_4") (pintype "input"))
      (node (ref "SV2") (pin "2") (pinfunction "2_2") (pintype "passive"))
      (node (ref "SV4") (pin "3") (pinfunction "3_3") (pintype "passive"))
      (node (ref "SV5") (pin "5") (pinfunction "5_5") (pintype "passive"))
      (node (ref "V1") (pin "1") (pinfunction "DIR_1") (pintype "input"))
      (node (ref "V1") (pin "20") (pinfunction "+UB_20") (pintype "power_in"))
      (node (ref "V2") (pin "20") (pinfunction "+UB_20") (pintype "power_in"))
    )
    (net (code "47") (name "Net-(IC15A-1A)") (class "Default")
      (node (ref "IC15") (pin "2") (pinfunction "1A_2") (pintype "input"))
      (node (ref "IC5") (pin "13") (pinfunction "13_13") (pintype "passive"))
    )
    (net (code "48") (name "Net-(IC15A-1B)") (class "Default")
      (node (ref "IC15") (pin "3") (pinfunction "1B_3") (pintype "input"))
      (node (ref "LED21") (pin "A") (pinfunction "A_A") (pintype "passive"))
      (node (ref "SV12") (pin "8") (pinfunction "8_8") (pintype "passive"))
    )
    (net (code "49") (name "Net-(IC15A-1Y)") (class "Default")
      (node (ref "IC1") (pin "1") (pinfunction "I_1") (pintype "input"))
      (node (ref "IC15") (pin "4") (pinfunction "1Y_4") (pintype "output"))
    )
    (net (code "50") (name "Net-(IC15A-2A)") (class "Default")
      (node (ref "IC15") (pin "5") (pinfunction "2A_5") (pintype "input"))
      (node (ref "IC5") (pin "14") (pinfunction "14_14") (pintype "passive"))
    )
    (net (code "51") (name "Net-(IC15A-2B)") (class "Default")
      (node (ref "IC15") (pin "6") (pinfunction "2B_6") (pintype "input"))
      (node (ref "LED20") (pin "A") (pinfunction "A_A") (pintype "passive"))
      (node (ref "SV12") (pin "7") (pinfunction "7_7") (pintype "passive"))
    )
    (net (code "52") (name "Net-(IC15A-2Y)") (class "Default")
      (node (ref "IC15") (pin "7") (pinfunction "2Y_7") (pintype "output"))
      (node (ref "SV2") (pin "1") (pinfunction "1_1") (pintype "passive"))
    )
    (net (code "53") (name "Net-(IC15A-3A)") (class "Default")
      (node (ref "IC15") (pin "11") (pinfunction "3A_11") (pintype "input"))
      (node (ref "IC5") (pin "15") (pinfunction "15_15") (pintype "passive"))
    )
    (net (code "54") (name "Net-(IC15A-3B)") (class "Default")
      (node (ref "IC15") (pin "10") (pinfunction "3B_10") (pintype "input"))
      (node (ref "LED19") (pin "A") (pinfunction "A_A") (pintype "passive"))
      (node (ref "SV12") (pin "6") (pinfunction "6_6") (pintype "passive"))
    )
    (net (code "55") (name "Net-(IC15A-3Y)") (class "Default")
      (node (ref "IC1") (pin "5") (pinfunction "I_5") (pintype "input"))
      (node (ref "IC15") (pin "9") (pinfunction "3Y_9") (pintype "output"))
    )
    (net (code "56") (name "Net-(IC15A-4A)") (class "Default")
      (node (ref "IC15") (pin "14") (pinfunction "4A_14") (pintype "input"))
      (node (ref "IC5") (pin "16") (pinfunction "16_16") (pintype "passive"))
    )
    (net (code "57") (name "Net-(IC15A-4B)") (class "Default")
      (node (ref "IC15") (pin "13") (pinfunction "4B_13") (pintype "input"))
      (node (ref "LED18") (pin "A") (pinfunction "A_A") (pintype "passive"))
      (node (ref "SV12") (pin "5") (pinfunction "5_5") (pintype "passive"))
    )
    (net (code "58") (name "Net-(IC15A-4Y)") (class "Default")
      (node (ref "IC15") (pin "12") (pinfunction "4Y_12") (pintype "output"))
      (node (ref "SV2") (pin "7") (pinfunction "7_7") (pintype "passive"))
    )
    (net (code "59") (name "Net-(IC16A-1A)") (class "Default")
      (node (ref "IC16") (pin "2") (pinfunction "1A_2") (pintype "input"))
      (node (ref "IC4") (pin "17") (pinfunction "17_17") (pintype "passive"))
    )
    (net (code "60") (name "Net-(IC16A-1B)") (class "Default")
      (node (ref "IC16") (pin "3") (pinfunction "1B_3") (pintype "input"))
      (node (ref "LED25") (pin "A") (pinfunction "A_A") (pintype "passive"))
      (node (ref "SV13") (pin "4") (pinfunction "4_4") (pintype "passive"))
    )
    (net (code "61") (name "Net-(IC16A-1Y)") (class "Default")
      (node (ref "IC16") (pin "4") (pinfunction "1Y_4") (pintype "output"))
      (node (ref "SV5") (pin "3") (pinfunction "3_3") (pintype "passive"))
    )
    (net (code "62") (name "Net-(IC16A-2A)") (class "Default")
      (node (ref "IC16") (pin "5") (pinfunction "2A_5") (pintype "input"))
      (node (ref "IC4") (pin "9") (pinfunction "9_9") (pintype "passive"))
    )
    (net (code "63") (name "Net-(IC16A-2B)") (class "Default")
      (node (ref "IC16") (pin "6") (pinfunction "2B_6") (pintype "input"))
      (node (ref "LED24") (pin "A") (pinfunction "A_A") (pintype "passive"))
      (node (ref "SV13") (pin "3") (pinfunction "3_3") (pintype "passive"))
    )
    (net (code "64") (name "Net-(IC16A-2Y)") (class "Default")
      (node (ref "IC16") (pin "7") (pinfunction "2Y_7") (pintype "output"))
      (node (ref "SV5") (pin "4") (pinfunction "4_4") (pintype "passive"))
    )
    (net (code "65") (name "Net-(IC16A-3A)") (class "Default")
      (node (ref "IC16") (pin "11") (pinfunction "3A_11") (pintype "input"))
      (node (ref "IC4") (pin "10") (pinfunction "10_10") (pintype "passive"))
    )
    (net (code "66") (name "Net-(IC16A-3B)") (class "Default")
      (node (ref "IC16") (pin "10") (pinfunction "3B_10") (pintype "input"))
      (node (ref "LED23") (pin "A") (pinfunction "A_A") (pintype "passive"))
      (node (ref "SV13") (pin "2") (pinfunction "2_2") (pintype "passive"))
    )
    (net (code "67") (name "Net-(IC16A-3Y)") (class "Default")
      (node (ref "IC16") (pin "9") (pinfunction "3Y_9") (pintype "output"))
      (node (ref "SV5") (pin "7") (pinfunction "7_7") (pintype "passive"))
    )
    (net (code "68") (name "Net-(IC16A-4A)") (class "Default")
      (node (ref "IC16") (pin "14") (pinfunction "4A_14") (pintype "input"))
      (node (ref "IC4") (pin "11") (pinfunction "11_11") (pintype "passive"))
    )
    (net (code "69") (name "Net-(IC16A-4B)") (class "Default")
      (node (ref "IC16") (pin "13") (pinfunction "4B_13") (pintype "input"))
      (node (ref "LED22") (pin "A") (pinfunction "A_A") (pintype "passive"))
      (node (ref "SV13") (pin "1") (pinfunction "1_1") (pintype "passive"))
    )
    (net (code "70") (name "Net-(IC16A-4Y)") (class "Default")
      (node (ref "IC16") (pin "12") (pinfunction "4Y_12") (pintype "output"))
      (node (ref "SV2") (pin "4") (pinfunction "4_4") (pintype "passive"))
    )
    (net (code "71") (name "Net-(IC17A-1A)") (class "Default")
      (node (ref "IC17") (pin "2") (pinfunction "1A_2") (pintype "input"))
      (node (ref "IC4") (pin "13") (pinfunction "13_13") (pintype "passive"))
    )
    (net (code "72") (name "Net-(IC17A-1B)") (class "Default")
      (node (ref "IC17") (pin "3") (pinfunction "1B_3") (pintype "input"))
      (node (ref "LED29") (pin "A") (pinfunction "A_A") (pintype "passive"))
      (node (ref "SV13") (pin "8") (pinfunction "8_8") (pintype "passive"))
    )
    (net (code "73") (name "Net-(IC17A-1Y)") (class "Default")
      (node (ref "IC17") (pin "4") (pinfunction "1Y_4") (pintype "output"))
      (node (ref "IC6") (pin "1") (pinfunction "CLR_1") (pintype "input"))
      (node (ref "IC6") (pin "13") (pinfunction "CLR_13") (pintype "input"))
      (node (ref "IC7") (pin "1") (pinfunction "CLR_1") (pintype "input"))
      (node (ref "IC7") (pin "13") (pinfunction "CLR_13") (pintype "input"))
    )
    (net (code "74") (name "Net-(IC17A-2A)") (class "Default")
      (node (ref "IC17") (pin "5") (pinfunction "2A_5") (pintype "input"))
      (node (ref "IC4") (pin "14") (pinfunction "14_14") (pintype "passive"))
    )
    (net (code "75") (name "Net-(IC17A-2B)") (class "Default")
      (node (ref "IC17") (pin "6") (pinfunction "2B_6") (pintype "input"))
      (node (ref "LED28") (pin "A") (pinfunction "A_A") (pintype "passive"))
      (node (ref "SV13") (pin "7") (pinfunction "7_7") (pintype "passive"))
    )
    (net (code "76") (name "Net-(IC17A-2Y)") (class "Default")
      (node (ref "IC17") (pin "7") (pinfunction "2Y_7") (pintype "output"))
      (node (ref "SV5") (pin "1") (pinfunction "1_1") (pintype "passive"))
    )
    (net (code "77") (name "Net-(IC17A-3A)") (class "Default")
      (node (ref "IC17") (pin "11") (pinfunction "3A_11") (pintype "input"))
      (node (ref "IC4") (pin "15") (pinfunction "15_15") (pintype "passive"))
    )
    (net (code "78") (name "Net-(IC17A-3B)") (class "Default")
      (node (ref "IC17") (pin "10") (pinfunction "3B_10") (pintype "input"))
      (node (ref "LED27") (pin "A") (pinfunction "A_A") (pintype "passive"))
      (node (ref "SV13") (pin "6") (pinfunction "6_6") (pintype "passive"))
    )
    (net (code "79") (name "Net-(IC17A-3Y)") (class "Default")
      (node (ref "IC17") (pin "9") (pinfunction "3Y_9") (pintype "output"))
      (node (ref "V1") (pin "19") (pinfunction "~{G}_19") (pintype "input"))
    )
    (net (code "80") (name "Net-(IC17A-4A)") (class "Default")
      (node (ref "IC17") (pin "14") (pinfunction "4A_14") (pintype "input"))
      (node (ref "IC4") (pin "16") (pinfunction "16_16") (pintype "passive"))
    )
    (net (code "81") (name "Net-(IC17A-4B)") (class "Default")
      (node (ref "IC17") (pin "13") (pinfunction "4B_13") (pintype "input"))
      (node (ref "LED26") (pin "A") (pinfunction "A_A") (pintype "passive"))
      (node (ref "SV13") (pin "5") (pinfunction "5_5") (pintype "passive"))
    )
    (net (code "82") (name "Net-(IC17A-4Y)") (class "Default")
      (node (ref "IC17") (pin "12") (pinfunction "4Y_12") (pintype "output"))
      (node (ref "SV5") (pin "2") (pinfunction "2_2") (pintype "passive"))
    )
    (net (code "83") (name "Net-(LED1-C)") (class "Default")
      (node (ref "LED1") (pin "K") (pinfunction "C_K") (pintype "passive"))
      (node (ref "RN3") (pin "9") (pinfunction "9_9") (pintype "passive"))
    )
    (net (code "84") (name "Net-(LED2-C)") (class "Default")
      (node (ref "LED2") (pin "K") (pinfunction "C_K") (pintype "passive"))
      (node (ref "RN3") (pin "8") (pinfunction "8_8") (pintype "passive"))
    )
    (net (code "85") (name "Net-(LED3-C)") (class "Default")
      (node (ref "LED3") (pin "K") (pinfunction "C_K") (pintype "passive"))
      (node (ref "RN3") (pin "7") (pinfunction "7_7") (pintype "passive"))
    )
    (net (code "86") (name "Net-(LED4-C)") (class "Default")
      (node (ref "LED4") (pin "K") (pinfunction "C_K") (pintype "passive"))
      (node (ref "RN3") (pin "6") (pinfunction "6_6") (pintype "passive"))
    )
    (net (code "87") (name "Net-(LED5-C)") (class "Default")
      (node (ref "LED5") (pin "K") (pinfunction "C_K") (pintype "passive"))
      (node (ref "RN3") (pin "5") (pinfunction "5_5") (pintype "passive"))
    )
    (net (code "88") (name "Net-(LED6-C)") (class "Default")
      (node (ref "LED6") (pin "K") (pinfunction "C_K") (pintype "passive"))
      (node (ref "RN3") (pin "4") (pinfunction "4_4") (pintype "passive"))
    )
    (net (code "89") (name "Net-(LED7-C)") (class "Default")
      (node (ref "LED7") (pin "K") (pinfunction "C_K") (pintype "passive"))
      (node (ref "RN3") (pin "3") (pinfunction "3_3") (pintype "passive"))
    )
    (net (code "90") (name "Net-(LED8-C)") (class "Default")
      (node (ref "LED8") (pin "K") (pinfunction "C_K") (pintype "passive"))
      (node (ref "RN3") (pin "2") (pinfunction "2_2") (pintype "passive"))
    )
    (net (code "91") (name "Net-(LED9-C)") (class "Default")
      (node (ref "LED9") (pin "K") (pinfunction "C_K") (pintype "passive"))
      (node (ref "R5") (pin "2") (pinfunction "2_2") (pintype "passive"))
    )
    (net (code "92") (name "Net-(LED10-C)") (class "Default")
      (node (ref "LED10") (pin "K") (pinfunction "C_K") (pintype "passive"))
      (node (ref "R6") (pin "2") (pinfunction "2_2") (pintype "passive"))
    )
    (net (code "93") (name "Net-(LED11-C)") (class "Default")
      (node (ref "LED11") (pin "K") (pinfunction "C_K") (pintype "passive"))
      (node (ref "R8") (pin "2") (pinfunction "2_2") (pintype "passive"))
    )
    (net (code "94") (name "Net-(LED12-C)") (class "Default")
      (node (ref "LED12") (pin "K") (pinfunction "C_K") (pintype "passive"))
      (node (ref "R17") (pin "2") (pinfunction "2_2") (pintype "passive"))
    )
    (net (code "95") (name "Net-(LED13-C)") (class "Default")
      (node (ref "LED13") (pin "K") (pinfunction "C_K") (pintype "passive"))
      (node (ref "RN1") (pin "2") (pinfunction "2_2") (pintype "passive"))
    )
    (net (code "96") (name "Net-(LED14-C)") (class "Default")
      (node (ref "LED14") (pin "K") (pinfunction "C_K") (pintype "passive"))
      (node (ref "RN1") (pin "3") (pinfunction "3_3") (pintype "passive"))
    )
    (net (code "97") (name "Net-(LED15-C)") (class "Default")
      (node (ref "LED15") (pin "K") (pinfunction "C_K") (pintype "passive"))
      (node (ref "RN1") (pin "4") (pinfunction "4_4") (pintype "passive"))
    )
    (net (code "98") (name "Net-(LED16-C)") (class "Default")
      (node (ref "LED16") (pin "K") (pinfunction "C_K") (pintype "passive"))
      (node (ref "RN1") (pin "5") (pinfunction "5_5") (pintype "passive"))
    )
    (net (code "99") (name "Net-(LED18-C)") (class "Default")
      (node (ref "LED18") (pin "K") (pinfunction "C_K") (pintype "passive"))
      (node (ref "RN1") (pin "6") (pinfunction "6_6") (pintype "passive"))
    )
    (net (code "100") (name "Net-(LED19-C)") (class "Default")
      (node (ref "LED19") (pin "K") (pinfunction "C_K") (pintype "passive"))
      (node (ref "RN1") (pin "7") (pinfunction "7_7") (pintype "passive"))
    )
    (net (code "101") (name "Net-(LED20-C)") (class "Default")
      (node (ref "LED20") (pin "K") (pinfunction "C_K") (pintype "passive"))
      (node (ref "RN1") (pin "8") (pinfunction "8_8") (pintype "passive"))
    )
    (net (code "102") (name "Net-(LED21-C)") (class "Default")
      (node (ref "LED21") (pin "K") (pinfunction "C_K") (pintype "passive"))
      (node (ref "RN1") (pin "9") (pinfunction "9_9") (pintype "passive"))
    )
    (net (code "103") (name "Net-(LED22-C)") (class "Default")
      (node (ref "LED22") (pin "K") (pinfunction "C_K") (pintype "passive"))
      (node (ref "RN2") (pin "2") (pinfunction "2_2") (pintype "passive"))
    )
    (net (code "104") (name "Net-(LED23-C)") (class "Default")
      (node (ref "LED23") (pin "K") (pinfunction "C_K") (pintype "passive"))
      (node (ref "RN2") (pin "3") (pinfunction "3_3") (pintype "passive"))
    )
    (net (code "105") (name "Net-(LED24-C)") (class "Default")
      (node (ref "LED24") (pin "K") (pinfunction "C_K") (pintype "passive"))
      (node (ref "RN2") (pin "4") (pinfunction "4_4") (pintype "passive"))
    )
    (net (code "106") (name "Net-(LED25-C)") (class "Default")
      (node (ref "LED25") (pin "K") (pinfunction "C_K") (pintype "passive"))
      (node (ref "RN2") (pin "5") (pinfunction "5_5") (pintype "passive"))
    )
    (net (code "107") (name "Net-(LED26-C)") (class "Default")
      (node (ref "LED26") (pin "K") (pinfunction "C_K") (pintype "passive"))
      (node (ref "RN2") (pin "6") (pinfunction "6_6") (pintype "passive"))
    )
    (net (code "108") (name "Net-(LED27-C)") (class "Default")
      (node (ref "LED27") (pin "K") (pinfunction "C_K") (pintype "passive"))
      (node (ref "RN2") (pin "7") (pinfunction "7_7") (pintype "passive"))
    )
    (net (code "109") (name "Net-(LED28-C)") (class "Default")
      (node (ref "LED28") (pin "K") (pinfunction "C_K") (pintype "passive"))
      (node (ref "RN2") (pin "8") (pinfunction "8_8") (pintype "passive"))
    )
    (net (code "110") (name "Net-(LED29-C)") (class "Default")
      (node (ref "LED29") (pin "K") (pinfunction "C_K") (pintype "passive"))
      (node (ref "RN2") (pin "9") (pinfunction "9_9") (pintype "passive"))
    )
    (net (code "111") (name "Net-(SV8-Pad3)") (class "Default")
      (node (ref "SV8") (pin "3") (pinfunction "3_3") (pintype "passive"))
      (node (ref "SV9") (pin "4") (pinfunction "4_4") (pintype "passive"))
    )
    (net (code "112") (name "Net-(SV8-Pad4)") (class "Default")
      (node (ref "SV8") (pin "4") (pinfunction "4_4") (pintype "passive"))
      (node (ref "SV9") (pin "3") (pinfunction "3_3") (pintype "passive"))
    )
    (net (code "113") (name "Net-(SV8-Pad5)") (class "Default")
      (node (ref "SV8") (pin "5") (pinfunction "5_5") (pintype "passive"))
      (node (ref "SV9") (pin "2") (pinfunction "2_2") (pintype "passive"))
    )
    (net (code "114") (name "Net-(SV8-Pad6)") (class "Default")
      (node (ref "SV8") (pin "6") (pinfunction "6_6") (pintype "passive"))
      (node (ref "SV9") (pin "1") (pinfunction "1_1") (pintype "passive"))
    )
    (net (code "115") (name "Net-(SV15-Pad1)") (class "Default")
      (node (ref "SV15") (pin "1") (pinfunction "1_1") (pintype "passive"))
      (node (ref "SV7") (pin "4") (pinfunction "4_4") (pintype "passive"))
    )
    (net (code "116") (name "Net-(SV15-Pad2)") (class "Default")
      (node (ref "SV15") (pin "2") (pinfunction "2_2") (pintype "passive"))
      (node (ref "SV7") (pin "3") (pinfunction "3_3") (pintype "passive"))
    )
    (net (code "117") (name "Net-(SV15-Pad3)") (class "Default")
      (node (ref "SV15") (pin "3") (pinfunction "3_3") (pintype "passive"))
      (node (ref "SV7") (pin "2") (pinfunction "2_2") (pintype "passive"))
    )
    (net (code "118") (name "Net-(SV15-Pad4)") (class "Default")
      (node (ref "SV15") (pin "4") (pinfunction "4_4") (pintype "passive"))
      (node (ref "SV7") (pin "1") (pinfunction "1_1") (pintype "passive"))
    )
    (net (code "119") (name "Net-(SV17-Pad1)") (class "Default")
      (node (ref "SV17") (pin "1") (pinfunction "1_1") (pintype "passive"))
      (node (ref "SV3") (pin "8") (pinfunction "8_8") (pintype "passive"))
    )
    (net (code "120") (name "Net-(SV17-Pad2)") (class "Default")
      (node (ref "SV17") (pin "2") (pinfunction "2_2") (pintype "passive"))
      (node (ref "SV3") (pin "7") (pinfunction "7_7") (pintype "passive"))
    )
    (net (code "121") (name "Net-(SV17-Pad3)") (class "Default")
      (node (ref "SV17") (pin "3") (pinfunction "3_3") (pintype "passive"))
      (node (ref "SV3") (pin "6") (pinfunction "6_6") (pintype "passive"))
    )
    (net (code "122") (name "Net-(SV17-Pad4)") (class "Default")
      (node (ref "SV17") (pin "4") (pinfunction "4_4") (pintype "passive"))
      (node (ref "SV3") (pin "5") (pinfunction "5_5") (pintype "passive"))
    )
    (net (code "123") (name "Net-(SV17-Pad5)") (class "Default")
      (node (ref "SV17") (pin "5") (pinfunction "5_5") (pintype "passive"))
      (node (ref "SV3") (pin "4") (pinfunction "4_4") (pintype "passive"))
    )
    (net (code "124") (name "Net-(SV17-Pad6)") (class "Default")
      (node (ref "SV17") (pin "6") (pinfunction "6_6") (pintype "passive"))
      (node (ref "SV3") (pin "3") (pinfunction "3_3") (pintype "passive"))
    )
    (net (code "125") (name "Net-(SV17-Pad7)") (class "Default")
      (node (ref "SV17") (pin "7") (pinfunction "7_7") (pintype "passive"))
      (node (ref "SV3") (pin "2") (pinfunction "2_2") (pintype "passive"))
    )
    (net (code "126") (name "Net-(SV17-Pad8)") (class "Default")
      (node (ref "SV17") (pin "8") (pinfunction "8_8") (pintype "passive"))
      (node (ref "SV3") (pin "1") (pinfunction "1_1") (pintype "passive"))
    )
    (net (code "127") (name "Net-(V1C-A1)") (class "Default")
      (node (ref "SV10") (pin "8") (pinfunction "8_8") (pintype "passive"))
      (node (ref "V1") (pin "2") (pinfunction "A1_2") (pintype "bidirectional"))
    )
    (net (code "128") (name "Net-(V1C-A2)") (class "Default")
      (node (ref "SV10") (pin "7") (pinfunction "7_7") (pintype "passive"))
      (node (ref "V1") (pin "3") (pinfunction "A2_3") (pintype "bidirectional"))
    )
    (net (code "129") (name "Net-(V1C-A3)") (class "Default")
      (node (ref "SV10") (pin "6") (pinfunction "6_6") (pintype "passive"))
      (node (ref "V1") (pin "4") (pinfunction "A3_4") (pintype "bidirectional"))
    )
    (net (code "130") (name "Net-(V1C-A4)") (class "Default")
      (node (ref "SV10") (pin "5") (pinfunction "5_5") (pintype "passive"))
      (node (ref "V1") (pin "5") (pinfunction "A4_5") (pintype "bidirectional"))
    )
    (net (code "131") (name "Net-(V1C-A5)") (class "Default")
      (node (ref "SV10") (pin "4") (pinfunction "4_4") (pintype "passive"))
      (node (ref "V1") (pin "6") (pinfunction "A5_6") (pintype "bidirectional"))
      (node (ref "V2") (pin "18") (pinfunction "B1_18") (pintype "bidirectional"))
    )
    (net (code "132") (name "Net-(V1C-A6)") (class "Default")
      (node (ref "SV10") (pin "3") (pinfunction "3_3") (pintype "passive"))
      (node (ref "V1") (pin "7") (pinfunction "A6_7") (pintype "bidirectional"))
      (node (ref "V2") (pin "17") (pinfunction "B2_17") (pintype "bidirectional"))
    )
    (net (code "133") (name "Net-(V1C-A7)") (class "Default")
      (node (ref "SV10") (pin "2") (pinfunction "2_2") (pintype "passive"))
      (node (ref "V1") (pin "8") (pinfunction "A7_8") (pintype "bidirectional"))
      (node (ref "V2") (pin "16") (pinfunction "B3_16") (pintype "bidirectional"))
    )
    (net (code "134") (name "Net-(V1C-A8)") (class "Default")
      (node (ref "SV10") (pin "1") (pinfunction "1_1") (pintype "passive"))
      (node (ref "V1") (pin "9") (pinfunction "A8_9") (pintype "bidirectional"))
      (node (ref "V2") (pin "15") (pinfunction "B4_15") (pintype "bidirectional"))
    )
    (net (code "135") (name "Net-(V1C-B1)") (class "Default")
      (node (ref "R16") (pin "1") (pinfunction "1_1") (pintype "passive"))
      (node (ref "V1") (pin "18") (pinfunction "B1_18") (pintype "bidirectional"))
    )
    (net (code "136") (name "Net-(V1C-B2)") (class "Default")
      (node (ref "R15") (pin "1") (pinfunction "1_1") (pintype "passive"))
      (node (ref "V1") (pin "17") (pinfunction "B2_17") (pintype "bidirectional"))
    )
    (net (code "137") (name "Net-(V1C-B3)") (class "Default")
      (node (ref "R14") (pin "1") (pinfunction "1_1") (pintype "passive"))
      (node (ref "V1") (pin "16") (pinfunction "B3_16") (pintype "bidirectional"))
    )
    (net (code "138") (name "Net-(V1C-B4)") (class "Default")
      (node (ref "R13") (pin "1") (pinfunction "1_1") (pintype "passive"))
      (node (ref "V1") (pin "15") (pinfunction "B4_15") (pintype "bidirectional"))
    )
    (net (code "139") (name "Net-(V1C-B5)") (class "Default")
      (node (ref "R4") (pin "1") (pinfunction "1_1") (pintype "passive"))
      (node (ref "V1") (pin "14") (pinfunction "B5_14") (pintype "bidirectional"))
    )
    (net (code "140") (name "Net-(V1C-B6)") (class "Default")
      (node (ref "R3") (pin "1") (pinfunction "1_1") (pintype "passive"))
      (node (ref "V1") (pin "13") (pinfunction "B6_13") (pintype "bidirectional"))
    )
    (net (code "141") (name "Net-(V1C-B7)") (class "Default")
      (node (ref "R2") (pin "1") (pinfunction "1_1") (pintype "passive"))
      (node (ref "V1") (pin "12") (pinfunction "B7_12") (pintype "bidirectional"))
    )
    (net (code "142") (name "Net-(V1C-B8)") (class "Default")
      (node (ref "R1") (pin "1") (pinfunction "1_1") (pintype "passive"))
      (node (ref "V1") (pin "11") (pinfunction "B8_11") (pintype "bidirectional"))
    )
    (net (code "143") (name "Net-(V2C-A1)") (class "Default")
      (node (ref "R12") (pin "1") (pinfunction "1_1") (pintype "passive"))
      (node (ref "V2") (pin "2") (pinfunction "A1_2") (pintype "bidirectional"))
    )
    (net (code "144") (name "Net-(V2C-A2)") (class "Default")
      (node (ref "R11") (pin "1") (pinfunction "1_1") (pintype "passive"))
      (node (ref "V2") (pin "3") (pinfunction "A2_3") (pintype "bidirectional"))
    )
    (net (code "145") (name "Net-(V2C-A3)") (class "Default")
      (node (ref "R10") (pin "1") (pinfunction "1_1") (pintype "passive"))
      (node (ref "V2") (pin "4") (pinfunction "A3_4") (pintype "bidirectional"))
    )
    (net (code "146") (name "Net-(V2C-A4)") (class "Default")
      (node (ref "R9") (pin "1") (pinfunction "1_1") (pintype "passive"))
      (node (ref "V2") (pin "5") (pinfunction "A4_5") (pintype "bidirectional"))
    )
    (net (code "147") (name "unconnected-(IC2A-~{Q}-Pad6)") (class "Default")
      (node (ref "IC2") (pin "6") (pinfunction "~{Q}_6") (pintype "output"))
    )
    (net (code "148") (name "unconnected-(IC2B-~{Q}-Pad8)") (class "Default")
      (node (ref "IC2") (pin "8") (pinfunction "~{Q}_8") (pintype "output"))
    )
    (net (code "149") (name "unconnected-(IC3A-~{Q}-Pad6)") (class "Default")
      (node (ref "IC3") (pin "6") (pinfunction "~{Q}_6") (pintype "output"))
    )
    (net (code "150") (name "unconnected-(IC3B-~{Q}-Pad8)") (class "Default")
      (node (ref "IC3") (pin "8") (pinfunction "~{Q}_8") (pintype "output"))
    )
    (net (code "151") (name "unconnected-(IC6A-~{Q}-Pad6)") (class "Default")
      (node (ref "IC6") (pin "6") (pinfunction "~{Q}_6") (pintype "output"))
    )
    (net (code "152") (name "unconnected-(IC6B-~{Q}-Pad8)") (class "Default")
      (node (ref "IC6") (pin "8") (pinfunction "~{Q}_8") (pintype "output"))
    )
    (net (code "153") (name "unconnected-(IC7A-~{Q}-Pad6)") (class "Default")
      (node (ref "IC7") (pin "6") (pinfunction "~{Q}_6") (pintype "output"))
    )
    (net (code "154") (name "unconnected-(IC7B-~{Q}-Pad8)") (class "Default")
      (node (ref "IC7") (pin "8") (pinfunction "~{Q}_8") (pintype "output"))
    )
    (net (code "155") (name "unconnected-(IC8A-~{Q}-Pad6)") (class "Default")
      (node (ref "IC8") (pin "6") (pinfunction "~{Q}_6") (pintype "output"))
    )
    (net (code "156") (name "unconnected-(IC8B-~{Q}-Pad8)") (class "Default")
      (node (ref "IC8") (pin "8") (pinfunction "~{Q}_8") (pintype "output"))
    )
    (net (code "157") (name "unconnected-(IC9A-~{Q}-Pad6)") (class "Default")
      (node (ref "IC9") (pin "6") (pinfunction "~{Q}_6") (pintype "output"))
    )
    (net (code "158") (name "unconnected-(IC9B-~{Q}-Pad8)") (class "Default")
      (node (ref "IC9") (pin "8") (pinfunction "~{Q}_8") (pintype "output"))
    )
    (net (code "159") (name "unconnected-(SV1-Pad1)") (class "Default")
      (node (ref "SV1") (pin "1") (pinfunction "1_1") (pintype "passive"))
    )
    (net (code "160") (name "unconnected-(SV1-Pad2)") (class "Default")
      (node (ref "SV1") (pin "2") (pinfunction "2_2") (pintype "passive"))
    )
    (net (code "161") (name "unconnected-(SV1-Pad3)") (class "Default")
      (node (ref "SV1") (pin "3") (pinfunction "3_3") (pintype "passive"))
    )
    (net (code "162") (name "unconnected-(SV1-Pad4)") (class "Default")
      (node (ref "SV1") (pin "4") (pinfunction "4_4") (pintype "passive"))
    )
    (net (code "163") (name "unconnected-(SV4-Pad1)") (class "Default")
      (node (ref "SV4") (pin "1") (pinfunction "1_1") (pintype "passive"))
    )
    (net (code "164") (name "unconnected-(SV5-Pad8)") (class "Default")
      (node (ref "SV5") (pin "8") (pinfunction "8_8") (pintype "passive"))
    )
    (net (code "165") (name "unconnected-(SV6-Pad1)") (class "Default")
      (node (ref "SV6") (pin "1") (pinfunction "1_1") (pintype "passive"))
    )
    (net (code "166") (name "unconnected-(SV6-Pad2)") (class "Default")
      (node (ref "SV6") (pin "2") (pinfunction "2_2") (pintype "passive"))
    )
    (net (code "167") (name "unconnected-(SV6-Pad3)") (class "Default")
      (node (ref "SV6") (pin "3") (pinfunction "3_3") (pintype "passive"))
    )
    (net (code "168") (name "unconnected-(SV8-Pad1)") (class "Default")
      (node (ref "SV8") (pin "1") (pinfunction "1_1") (pintype "passive"))
    )
    (net (code "169") (name "unconnected-(SV8-Pad2)") (class "Default")
      (node (ref "SV8") (pin "2") (pinfunction "2_2") (pintype "passive"))
    )
    (net (code "170") (name "unconnected-(SV9-Pad5)") (class "Default")
      (node (ref "SV9") (pin "5") (pinfunction "5_5") (pintype "passive"))
    )
    (net (code "171") (name "unconnected-(SV9-Pad6)") (class "Default")
      (node (ref "SV9") (pin "6") (pinfunction "6_6") (pintype "passive"))
    )
    (net (code "172") (name "unconnected-(V2C-A5-Pad6)") (class "Default")
      (node (ref "V2") (pin "6") (pinfunction "A5_6") (pintype "bidirectional"))
    )
    (net (code "173") (name "unconnected-(V2C-A6-Pad7)") (class "Default")
      (node (ref "V2") (pin "7") (pinfunction "A6_7") (pintype "bidirectional"))
    )
    (net (code "174") (name "unconnected-(V2C-A7-Pad8)") (class "Default")
      (node (ref "V2") (pin "8") (pinfunction "A7_8") (pintype "bidirectional"))
    )
    (net (code "175") (name "unconnected-(V2C-A8-Pad9)") (class "Default")
      (node (ref "V2") (pin "9") (pinfunction "A8_9") (pintype "bidirectional"))
    )
    (net (code "176") (name "unconnected-(V2C-B5-Pad14)") (class "Default")
      (node (ref "V2") (pin "14") (pinfunction "B5_14") (pintype "bidirectional"))
    )
    (net (code "177") (name "unconnected-(V2C-B6-Pad13)") (class "Default")
      (node (ref "V2") (pin "13") (pinfunction "B6_13") (pintype "bidirectional"))
    )
    (net (code "178") (name "unconnected-(V2C-B7-Pad12)") (class "Default")
      (node (ref "V2") (pin "12") (pinfunction "B7_12") (pintype "bidirectional"))
    )
    (net (code "179") (name "unconnected-(V2C-B8-Pad11)") (class "Default")
      (node (ref "V2") (pin "11") (pinfunction "B8_11") (pintype "bidirectional"))
    )
  )
)
